# VoltageBooster48V.net
KiCad netlist of a schematic drawn in Altium Designer
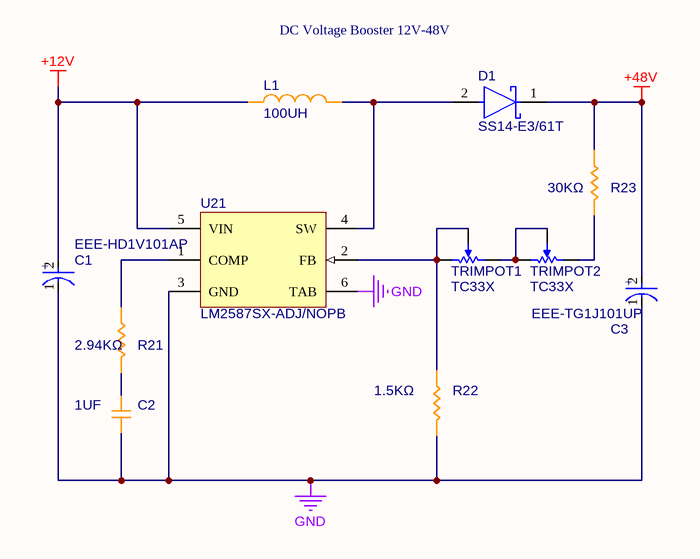
[diagram p0: VoltageBooster48V.SchDoc]

(export (version "E")
  (design (tool "Eeschema 10.0.6"))
  (components
    (comp (ref "C1")
      (value "EEE-HD1V101AP")
      (footprint "FP-HDG-MFG")
      (fields (field (name "VOLTAGE") "35V") (field (name "TOLERANCE") "20%"))
      (libsource (lib "Altium Content Vault") (part "203bc49f2ac43e59fd269a8c329ed05"))
    )
    (comp (ref "C2")
      (value "1UF")
      (footprint "CAP_0603")
      (description "Capacitor SMD 0603 generic")
      (libsource (lib "GenericRC") (part "CAP_0603"))
    )
    (comp (ref "C3")
      (value "EEE-TG1J101UP")
      (footprint "FP-TGG-MFG")
      (description "CAP ALUM 100UF 20% 63V SMD")
      (fields (field (name "VOLTAGE") "63V") (field (name "TOLERANCE") "20%"))
      (libsource (lib "Altium Content Vault") (part "203bc49f2ac43e59fd269a8c329ed05"))
    )
    (comp (ref "D1")
      (value "SS14-E3/61T")
      (footprint "FP-95400-MFG")
      (description "DIODE SCHOTTKY 40V 1A DO214AC")
      (fields
        (field (name "OCTOPART") "https://octopart.com/ss14-e3%2F61t-vishay-39552847")
        (field (name "MANUFACTURER") "Vishay")
      )
      (libsource (lib "Altium Content Vault") (part "1d6ec82d83fb6aee721767c19dac4b9"))
    )
    (comp (ref "L1")
      (value "100UH")
      (footprint "IND_Boost")
      (description "Voltage Boost Inductor")
      (libsource (lib "GenericRC") (part "Boost Inductor"))
    )
    (comp (ref "R21")
      (value "2.94KΩ")
      (footprint "RES_0603")
      (description "Resistor SMD 0603 generic")
      (libsource (lib "GenericRC") (part "RES_0603"))
    )
    (comp (ref "R22")
      (value "1.5KΩ")
      (footprint "RES_0603")
      (description "Resistor SMD 0603 generic")
      (libsource (lib "GenericRC") (part "RES_0603"))
    )
    (comp (ref "R23")
      (value "30KΩ")
      (footprint "RES_0603")
      (description "Resistor SMD 0603 generic")
      (libsource (lib "GenericRC") (part "RES_0603"))
    )
    (comp (ref "TRIMPOT1")
      (value "TC33X")
      (footprint "BOUR-TC33X-2_V")
      (description "Trimming Potentiometer, 10000 Ohm, -40 to 100 degC, 3-Pin SMD, RoHS, Tape and Reel")
      (fields (field (name "TOLERANCE") "25%") (field (name "MANUFACTURER") "Bourns"))
      (libsource (lib "Altium Content Vault") (part "RES-ADJ-3_A"))
    )
    (comp (ref "TRIMPOT2")
      (value "TC33X")
      (footprint "BOUR-TC33X-2_V")
      (description "Trimming Potentiometer, 10000 Ohm, -40 to 100 degC, 3-Pin SMD, RoHS, Tape and Reel")
      (fields (field (name "TOLERANCE") "25%") (field (name "MANUFACTURER") "Bourns"))
      (libsource (lib "Altium Content Vault") (part "RES-ADJ-3_A"))
    )
    (comp (ref "U21")
      (value "LM2587SX-ADJ/NOPB")
      (footprint "KTT0005B_N")
      (description "5A Flyback Regulator, 5-pin TO-263, Pb-Free")
      (fields (field (name "MANUFACTURER") "Texas Instruments"))
      (libsource (lib "Altium Content Vault") (part "PM-SWREG-LM2585S-12"))
    )
  )
  (nets
    (net (code "1") (name "+12V") (class "Default")
      (node (ref "C1") (pin "2") (pinfunction "A_2") (pintype "passive"))
      (node (ref "L1") (pin "1") (pintype "passive"))
      (node (ref "U21") (pin "5") (pinfunction "VIN_5") (pintype "power_in"))
    )
    (net (code "2") (name "+48V") (class "Default")
      (node (ref "C3") (pin "2") (pinfunction "A_2") (pintype "passive"))
      (node (ref "D1") (pin "1") (pinfunction "C_1") (pintype "passive"))
      (node (ref "R23") (pin "2") (pintype "passive"))
    )
    (net (code "3") (name "GND") (class "Default")
      (node (ref "C1") (pin "1") (pinfunction "C_1") (pintype "passive"))
      (node (ref "C2") (pin "1") (pintype "passive"))
      (node (ref "C3") (pin "1") (pinfunction "C_1") (pintype "passive"))
      (node (ref "R22") (pin "1") (pintype "passive"))
      (node (ref "U21") (pin "3") (pinfunction "GND_3") (pintype "power_in"))
      (node (ref "U21") (pin "6") (pinfunction "TAB_6") (pintype "passive"))
    )
    (net (code "4") (name "Net-(C2-Pad2)") (class "Default")
      (node (ref "C2") (pin "2") (pintype "passive"))
      (node (ref "R21") (pin "1") (pintype "passive"))
    )
    (net (code "5") (name "Net-(D1-A)") (class "Default")
      (node (ref "D1") (pin "2") (pinfunction "A_2") (pintype "passive"))
      (node (ref "L1") (pin "2") (pintype "passive"))
      (node (ref "U21") (pin "4") (pinfunction "SW_4") (pintype "power_in"))
    )
    (net (code "6") (name "Net-(R23-Pad1)") (class "Default")
      (node (ref "R23") (pin "1") (pintype "passive"))
      (node (ref "TRIMPOT2") (pin "3") (pinfunction "3_3") (pintype "passive"))
    )
    (net (code "7") (name "Net-(TRIMPOT1-Pad3)") (class "Default")
      (node (ref "TRIMPOT1") (pin "3") (pinfunction "3_3") (pintype "passive"))
      (node (ref "TRIMPOT2") (pin "1") (pinfunction "1_1") (pintype "passive"))
      (node (ref "TRIMPOT2") (pin "2") (pinfunction "2_2") (pintype "passive"))
    )
    (net (code "8") (name "Net-(U21-COMP)") (class "Default")
      (node (ref "R21") (pin "2") (pintype "passive"))
      (node (ref "U21") (pin "1") (pinfunction "COMP_1") (pintype "passive"))
    )
    (net (code "9") (name "Net-(U21-FB)") (class "Default")
      (node (ref "R22") (pin "2") (pintype "passive"))
      (node (ref "TRIMPOT1") (pin "1") (pinfunction "1_1") (pintype "passive"))
      (node (ref "TRIMPOT1") (pin "2") (pinfunction "2_2") (pintype "passive"))
      (node (ref "U21") (pin "2") (pinfunction "FB_2") (pintype "input"))
    )
  )
)
